# PSU15VRTR.net
KiCad netlist of a schematic drawn in EAGLE
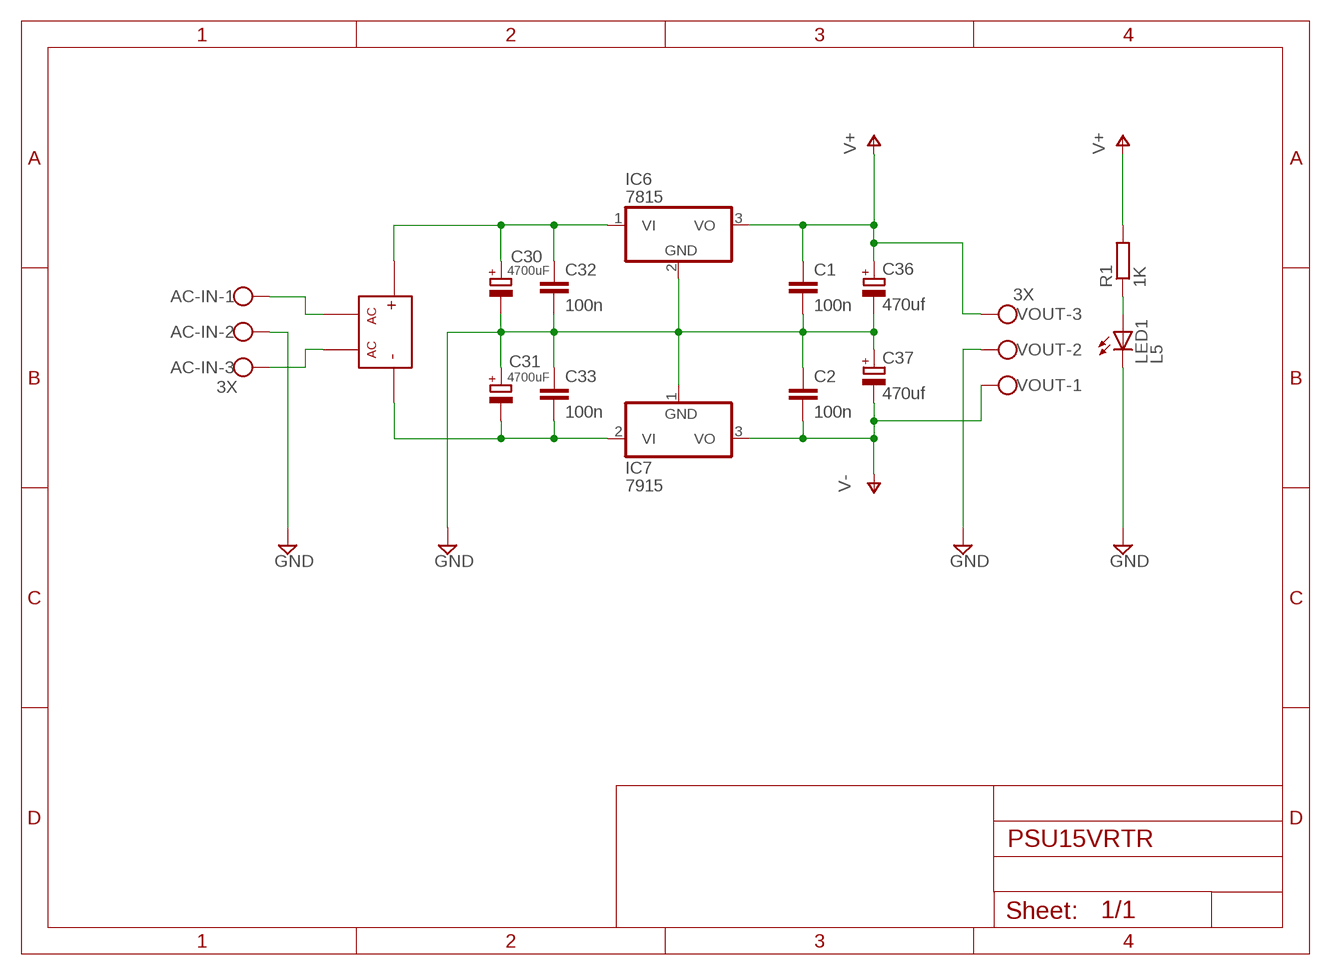
[diagram p0: schematic, sheet 1]

(export (version "E")
  (design (tool "Eeschema 10.0.6"))
  (components
    (comp (ref "AC-IN")
      (value "3X")
      (footprint "eagle-import:W237-103")
      (fields (field (name "MPN") "237-103"))
      (libsource (lib "eagle-import") (part "W237-103"))
    )
    (comp (ref "C1")
      (value "100n")
      (footprint "eagle-import:C050-025X075")
      (libsource (lib "eagle-import") (part "C-EU050-025X075"))
    )
    (comp (ref "C2")
      (value "100n")
      (footprint "eagle-import:C050-025X075")
      (libsource (lib "eagle-import") (part "C-EU050-025X075"))
    )
    (comp (ref "C30")
      (value "4700uF")
      (footprint "eagle-import:E7,5-18")
      (libsource (lib "eagle-import") (part "CPOL-EUE7.5-18"))
    )
    (comp (ref "C31")
      (value "4700uF")
      (footprint "eagle-import:E7,5-18")
      (libsource (lib "eagle-import") (part "CPOL-EUE7.5-18"))
    )
    (comp (ref "C32")
      (value "100n")
      (footprint "eagle-import:C050-025X075")
      (libsource (lib "eagle-import") (part "C-EU050-025X075"))
    )
    (comp (ref "C33")
      (value "100n")
      (footprint "eagle-import:C050-025X075")
      (libsource (lib "eagle-import") (part "C-EU050-025X075"))
    )
    (comp (ref "C36")
      (value "470uf")
      (footprint "eagle-import:E3,5-8")
      (libsource (lib "eagle-import") (part "CPOL-EUE3.5-8"))
    )
    (comp (ref "C37")
      (value "470uf")
      (footprint "eagle-import:E3,5-8")
      (libsource (lib "eagle-import") (part "CPOL-EUE3.5-8"))
    )
    (comp (ref "IC6")
      (value "7815")
      (footprint "eagle-import:TO220H")
      (libsource (lib "eagle-import") (part "78T15"))
    )
    (comp (ref "IC7")
      (value "7915")
      (footprint "eagle-import:TO220H")
      (libsource (lib "eagle-import") (part "79T15"))
    )
    (comp (ref "LED1")
      (value "L5")
      (footprint "eagle-import:LED5MM")
      (libsource (lib "eagle-import") (part "LED5MM"))
    )
    (comp (ref "R1")
      (value "1K")
      (footprint "eagle-import:0204_7")
      (libsource (lib "eagle-import") (part "R-EU_0204/7"))
    )
    (comp (ref "REC1")
      (value "RECTIFIER")
      (footprint "eagle-import:RECTIFIER")
      (libsource (lib "eagle-import") (part "RECTIFIER"))
    )
    (comp (ref "VOUT")
      (value "3X")
      (footprint "eagle-import:W237-103")
      (fields (field (name "MPN") "237-103"))
      (libsource (lib "eagle-import") (part "W237-103"))
    )
  )
  (nets
    (net (code "1") (name "GND") (class "Default")
      (node (ref "AC-IN") (pin "2") (pinfunction "KL_2") (pintype "passive"))
      (node (ref "C1") (pin "2") (pinfunction "2_2") (pintype "passive"))
      (node (ref "C2") (pin "1") (pinfunction "1_1") (pintype "passive"))
      (node (ref "C30") (pin "-") (pinfunction "-_-") (pintype "passive"))
      (node (ref "C31") (pin "+") (pinfunction "+_+") (pintype "passive"))
      (node (ref "C32") (pin "2") (pinfunction "2_2") (pintype "passive"))
      (node (ref "C33") (pin "1") (pinfunction "1_1") (pintype "passive"))
      (node (ref "C36") (pin "-") (pinfunction "-_-") (pintype "passive"))
      (node (ref "C37") (pin "+") (pinfunction "+_+") (pintype "passive"))
      (node (ref "IC6") (pin "2") (pinfunction "GND_2") (pintype "passive"))
      (node (ref "IC7") (pin "1") (pinfunction "GND_1") (pintype "passive"))
      (node (ref "LED1") (pin "K") (pinfunction "C_K") (pintype "passive"))
      (node (ref "VOUT") (pin "2") (pinfunction "KL_2") (pintype "passive"))
    )
    (net (code "2") (name "Net-(AC-INA-KL)") (class "Default")
      (node (ref "AC-IN") (pin "1") (pinfunction "KL_1") (pintype "passive"))
      (node (ref "REC1") (pin "AC1") (pinfunction "AC1_AC1") (pintype "bidirectional"))
    )
    (net (code "3") (name "Net-(AC-INC-KL)") (class "Default")
      (node (ref "AC-IN") (pin "3") (pinfunction "KL_3") (pintype "passive"))
      (node (ref "REC1") (pin "AC0") (pinfunction "AC0_AC0") (pintype "bidirectional"))
    )
    (net (code "4") (name "Net-(IC6-VI)") (class "Default")
      (node (ref "C30") (pin "+") (pinfunction "+_+") (pintype "passive"))
      (node (ref "C32") (pin "1") (pinfunction "1_1") (pintype "passive"))
      (node (ref "IC6") (pin "1") (pinfunction "VI_1") (pintype "input"))
      (node (ref "REC1") (pin "P") (pinfunction "P_P") (pintype "bidirectional"))
    )
    (net (code "5") (name "Net-(IC7-VI)") (class "Default")
      (node (ref "C31") (pin "-") (pinfunction "-_-") (pintype "passive"))
      (node (ref "C33") (pin "2") (pinfunction "2_2") (pintype "passive"))
      (node (ref "IC7") (pin "2") (pinfunction "VI_2") (pintype "input"))
      (node (ref "REC1") (pin "N") (pinfunction "N_N") (pintype "bidirectional"))
    )
    (net (code "6") (name "Net-(LED1-PadA)") (class "Default")
      (node (ref "LED1") (pin "A") (pinfunction "A_A") (pintype "passive"))
      (node (ref "R1") (pin "1") (pinfunction "1_1") (pintype "passive"))
    )
    (net (code "7") (name "V+") (class "Default")
      (node (ref "C1") (pin "1") (pinfunction "1_1") (pintype "passive"))
      (node (ref "C36") (pin "+") (pinfunction "+_+") (pintype "passive"))
      (node (ref "IC6") (pin "3") (pinfunction "VO_3") (pintype "passive"))
      (node (ref "R1") (pin "2") (pinfunction "2_2") (pintype "passive"))
      (node (ref "VOUT") (pin "3") (pinfunction "KL_3") (pintype "passive"))
    )
    (net (code "8") (name "V-") (class "Default")
      (node (ref "C2") (pin "2") (pinfunction "2_2") (pintype "passive"))
      (node (ref "C37") (pin "-") (pinfunction "-_-") (pintype "passive"))
      (node (ref "IC7") (pin "3") (pinfunction "VO_3") (pintype "passive"))
      (node (ref "VOUT") (pin "1") (pinfunction "KL_1") (pintype "passive"))
    )
  )
)
